# 12_QSPI_SD-Card.net
KiCad netlist of a schematic drawn in Altium Designer
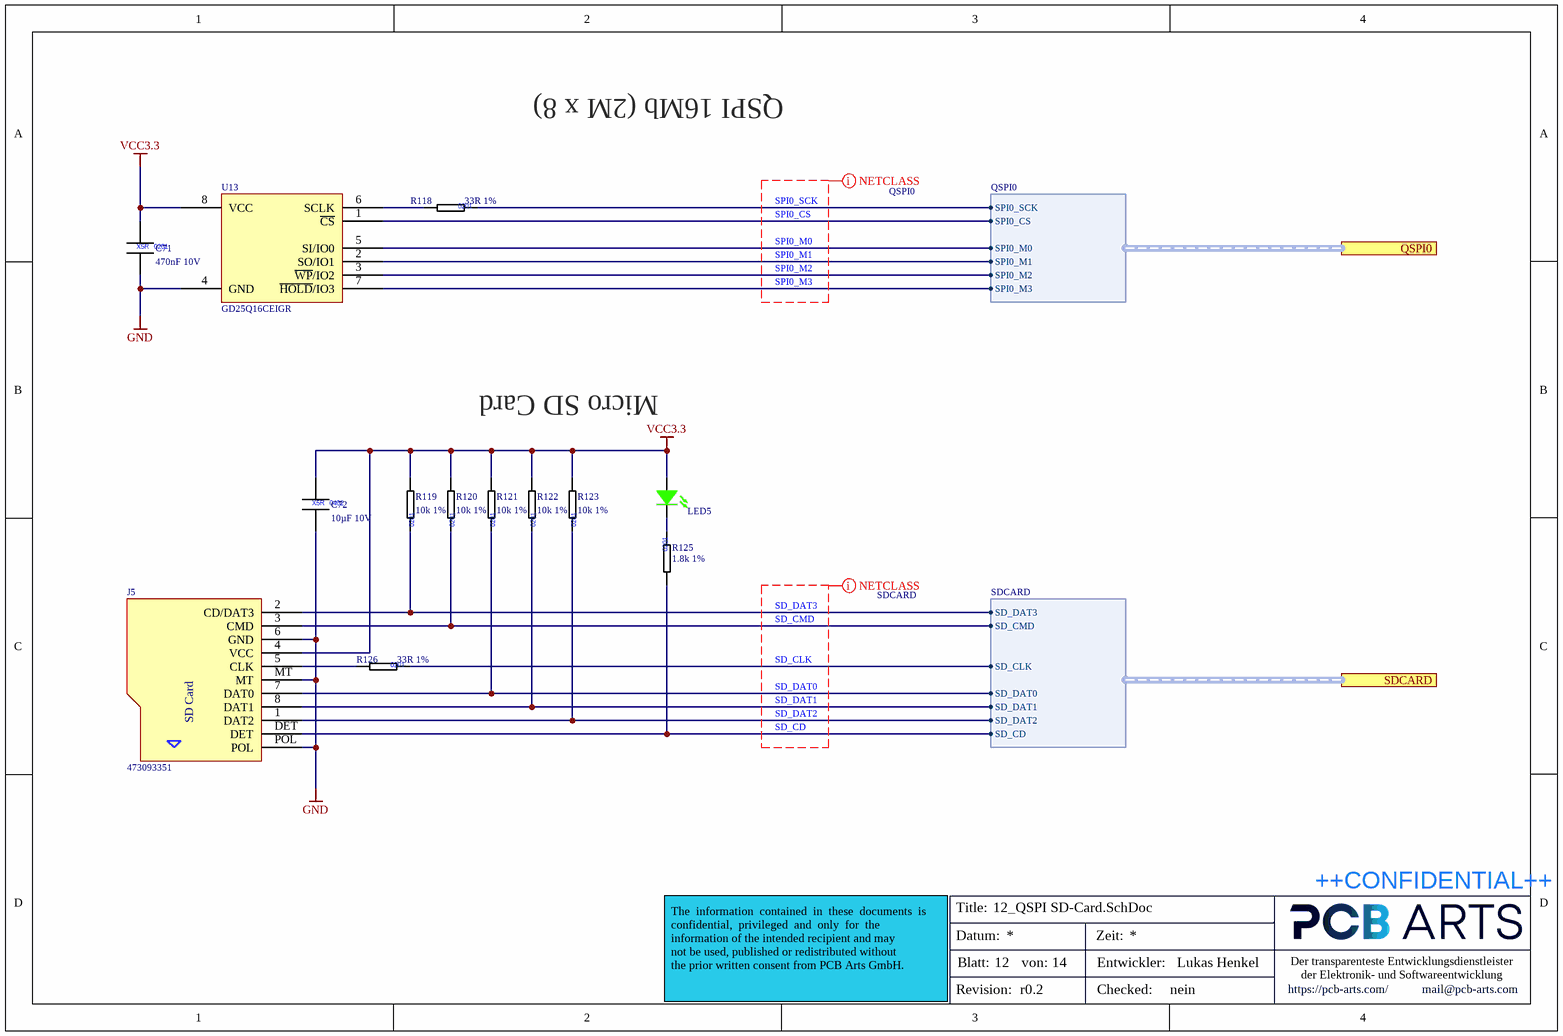
[diagram p0: 12_QSPI SD-Card.SchDoc]

(export (version "E")
  (design (tool "Eeschema 10.0.6"))
  (components
    (comp (ref "C71")
      (value "470nF 10V")
      (footprint "Zynq-Feather-HD:CAPC0603X03L")
      (description "Multilayer Ceramic Capacitors MLCC - SMD/SMT 0201 10VDC")
      (libsource (lib "Zynq-Feather-HD") (part "CAP_0201_470nF_10V"))
    )
    (comp (ref "C72")
      (value "10µF 10V")
      (footprint "Zynq-Feather-HD:CAPC1005X06L")
      (description "Multilayer Ceramic Capacitors MLCC - SMD/SMT 0402 10VDC")
      (libsource (lib "Zynq-Feather-HD") (part "CAP_0402_10µ_10V"))
    )
    (comp (ref "J5")
      (value "473093351")
      (footprint "Zynq-Feather-HD:47309-3351")
      (description "1.10mm Pitch microSD Card Header with Detect Switch, Height 3.35mm, Lead-Free")
      (libsource (lib "Zynq-Feather-HD") (part "473093351_1.10mm Pitch microSD Card Header"))
    )
    (comp (ref "LED5")
      (value "150040GS73220")
      (footprint "Zynq-Feather-HD:WL-SMCC_0402_H=0.25mm")
      (description "Standard LEDs - SMD WL-SMCC SMT LED Mono-color")
      (libsource (lib "Zynq-Feather-HD") (part "150040GS73220_SMD WL-SMCC SMT LED Mono-color"))
    )
    (comp (ref "R118")
      (value "33R 1%")
      (footprint "Zynq-Feather-HD:RESC0603X03L")
      (description "Thick Film Resistors - SMD 33R OHM 1%")
      (libsource (lib "Zynq-Feather-HD") (part "RES_0201_33R_1%"))
    )
    (comp (ref "R119")
      (value "10k 1%")
      (footprint "Zynq-Feather-HD:RESC0603X03L")
      (description "Thick Film Resistors - SMD 10K OHM 1%")
      (libsource (lib "Zynq-Feather-HD") (part "RES_0201_10k_1%"))
    )
    (comp (ref "R120")
      (value "10k 1%")
      (footprint "Zynq-Feather-HD:RESC0603X03L")
      (description "Thick Film Resistors - SMD 10K OHM 1%")
      (libsource (lib "Zynq-Feather-HD") (part "RES_0201_10k_1%"))
    )
    (comp (ref "R121")
      (value "10k 1%")
      (footprint "Zynq-Feather-HD:RESC0603X03L")
      (description "Thick Film Resistors - SMD 10K OHM 1%")
      (libsource (lib "Zynq-Feather-HD") (part "RES_0201_10k_1%"))
    )
    (comp (ref "R122")
      (value "10k 1%")
      (footprint "Zynq-Feather-HD:RESC0603X03L")
      (description "Thick Film Resistors - SMD 10K OHM 1%")
      (libsource (lib "Zynq-Feather-HD") (part "RES_0201_10k_1%"))
    )
    (comp (ref "R123")
      (value "10k 1%")
      (footprint "Zynq-Feather-HD:RESC0603X03L")
      (description "Thick Film Resistors - SMD 10K OHM 1%")
      (libsource (lib "Zynq-Feather-HD") (part "RES_0201_10k_1%"))
    )
    (comp (ref "R125")
      (value "1.8k 1%")
      (footprint "Zynq-Feather-HD:RESC0603X03L")
      (description "Thick Film Resistors - SMD 1.8K OHM 1%")
      (libsource (lib "Zynq-Feather-HD") (part "RES_0201_1.8k_1%"))
    )
    (comp (ref "R126")
      (value "33R 1%")
      (footprint "Zynq-Feather-HD:RESC0603X03L")
      (description "Thick Film Resistors - SMD 33R OHM 1%")
      (libsource (lib "Zynq-Feather-HD") (part "RES_0201_33R_1%"))
    )
    (comp (ref "U13")
      (value "GD25Q16CEIGR")
      (footprint "Zynq-Feather-HD:PSON50P300X50_HS-9N")
      (description "NOR Flash 16Mbit NOR Flash /3.3V /WSON 3*2*0.45mm /Industrial(-40 to +85 ) /T&R")
      (libsource (lib "Zynq-Feather-HD") (part "GD25Q16CEIGR_NOR Flash 16Mbit"))
    )
  )
  (nets
    (net (code "3") (name "/SD_CD") (class "Default")
      (node (ref "J5") (pin "DET") (pinfunction "DET_DET") (pintype "passive"))
      (node (ref "R125") (pin "2") (pinfunction "2_2") (pintype "passive"))
    )
    (net (code "4") (name "/SD_CLK") (class "Default")
      (node (ref "R126") (pin "1") (pinfunction "1_1") (pintype "passive"))
    )
    (net (code "5") (name "/SD_CMD") (class "Default")
      (node (ref "J5") (pin "3") (pinfunction "CMD_3") (pintype "passive"))
      (node (ref "R120") (pin "1") (pinfunction "1_1") (pintype "passive"))
    )
    (net (code "6") (name "/SD_DAT0") (class "Default")
      (node (ref "J5") (pin "7") (pinfunction "DAT0_7") (pintype "passive"))
      (node (ref "R121") (pin "1") (pinfunction "1_1") (pintype "passive"))
    )
    (net (code "7") (name "/SD_DAT1") (class "Default")
      (node (ref "J5") (pin "8") (pinfunction "DAT1_8") (pintype "passive"))
      (node (ref "R122") (pin "1") (pinfunction "1_1") (pintype "passive"))
    )
    (net (code "8") (name "/SD_DAT2") (class "Default")
      (node (ref "J5") (pin "1") (pinfunction "DAT2_1") (pintype "passive"))
      (node (ref "R123") (pin "1") (pinfunction "1_1") (pintype "passive"))
    )
    (net (code "9") (name "/SD_DAT3") (class "Default")
      (node (ref "J5") (pin "2") (pinfunction "CD/DAT3_2") (pintype "passive"))
      (node (ref "R119") (pin "1") (pinfunction "1_1") (pintype "passive"))
    )
    (net (code "10") (name "/SPI0_CS") (class "Default")
      (node (ref "U13") (pin "1") (pinfunction "~{CS}_1") (pintype "passive"))
    )
    (net (code "11") (name "/SPI0_M0") (class "Default")
      (node (ref "U13") (pin "5") (pinfunction "SI/IO0_5") (pintype "passive"))
    )
    (net (code "12") (name "/SPI0_M1") (class "Default")
      (node (ref "U13") (pin "2") (pinfunction "SO/IO1_2") (pintype "passive"))
    )
    (net (code "13") (name "/SPI0_M2") (class "Default")
      (node (ref "U13") (pin "3") (pinfunction "~{WP}/IO2_3") (pintype "passive"))
    )
    (net (code "14") (name "/SPI0_M3") (class "Default")
      (node (ref "U13") (pin "7") (pinfunction "~{HOLD}/IO3_7") (pintype "passive"))
    )
    (net (code "15") (name "/SPI0_SCK") (class "Default")
      (node (ref "R118") (pin "1") (pinfunction "1_1") (pintype "passive"))
    )
    (net (code "18") (name "GND") (class "Default")
      (node (ref "C71") (pin "2") (pinfunction "2_2") (pintype "passive"))
      (node (ref "C72") (pin "2") (pinfunction "2_2") (pintype "passive"))
      (node (ref "J5") (pin "6") (pinfunction "GND_6") (pintype "passive"))
      (node (ref "J5") (pin "MT") (pinfunction "MT_MT") (pintype "passive"))
      (node (ref "J5") (pin "POL") (pinfunction "POL_POL") (pintype "passive"))
      (node (ref "U13") (pin "4") (pinfunction "GND_4") (pintype "passive"))
    )
    (net (code "19") (name "Net-(J5-CLK)") (class "Default")
      (node (ref "J5") (pin "5") (pinfunction "CLK_5") (pintype "passive"))
      (node (ref "R126") (pin "2") (pinfunction "2_2") (pintype "passive"))
    )
    (net (code "20") (name "Net-(LED5-Pad1)") (class "Default")
      (node (ref "LED5") (pin "1") (pinfunction "1_1") (pintype "passive"))
      (node (ref "R125") (pin "1") (pinfunction "1_1") (pintype "passive"))
    )
    (net (code "21") (name "Net-(U13-SCLK)") (class "Default")
      (node (ref "R118") (pin "2") (pinfunction "2_2") (pintype "passive"))
      (node (ref "U13") (pin "6") (pinfunction "SCLK_6") (pintype "passive"))
    )
    (net (code "22") (name "VCC3.3") (class "Default")
      (node (ref "C71") (pin "1") (pinfunction "1_1") (pintype "passive"))
      (node (ref "C72") (pin "1") (pinfunction "1_1") (pintype "passive"))
      (node (ref "J5") (pin "4") (pinfunction "VCC_4") (pintype "passive"))
      (node (ref "LED5") (pin "2") (pinfunction "2_2") (pintype "passive"))
      (node (ref "R119") (pin "2") (pinfunction "2_2") (pintype "passive"))
      (node (ref "R120") (pin "2") (pinfunction "2_2") (pintype "passive"))
      (node (ref "R121") (pin "2") (pinfunction "2_2") (pintype "passive"))
      (node (ref "R122") (pin "2") (pinfunction "2_2") (pintype "passive"))
      (node (ref "R123") (pin "2") (pinfunction "2_2") (pintype "passive"))
      (node (ref "U13") (pin "8") (pinfunction "VCC_8") (pintype "passive"))
    )
  )
)
